# Controller.net
KiCad netlist of a schematic drawn in EAGLE
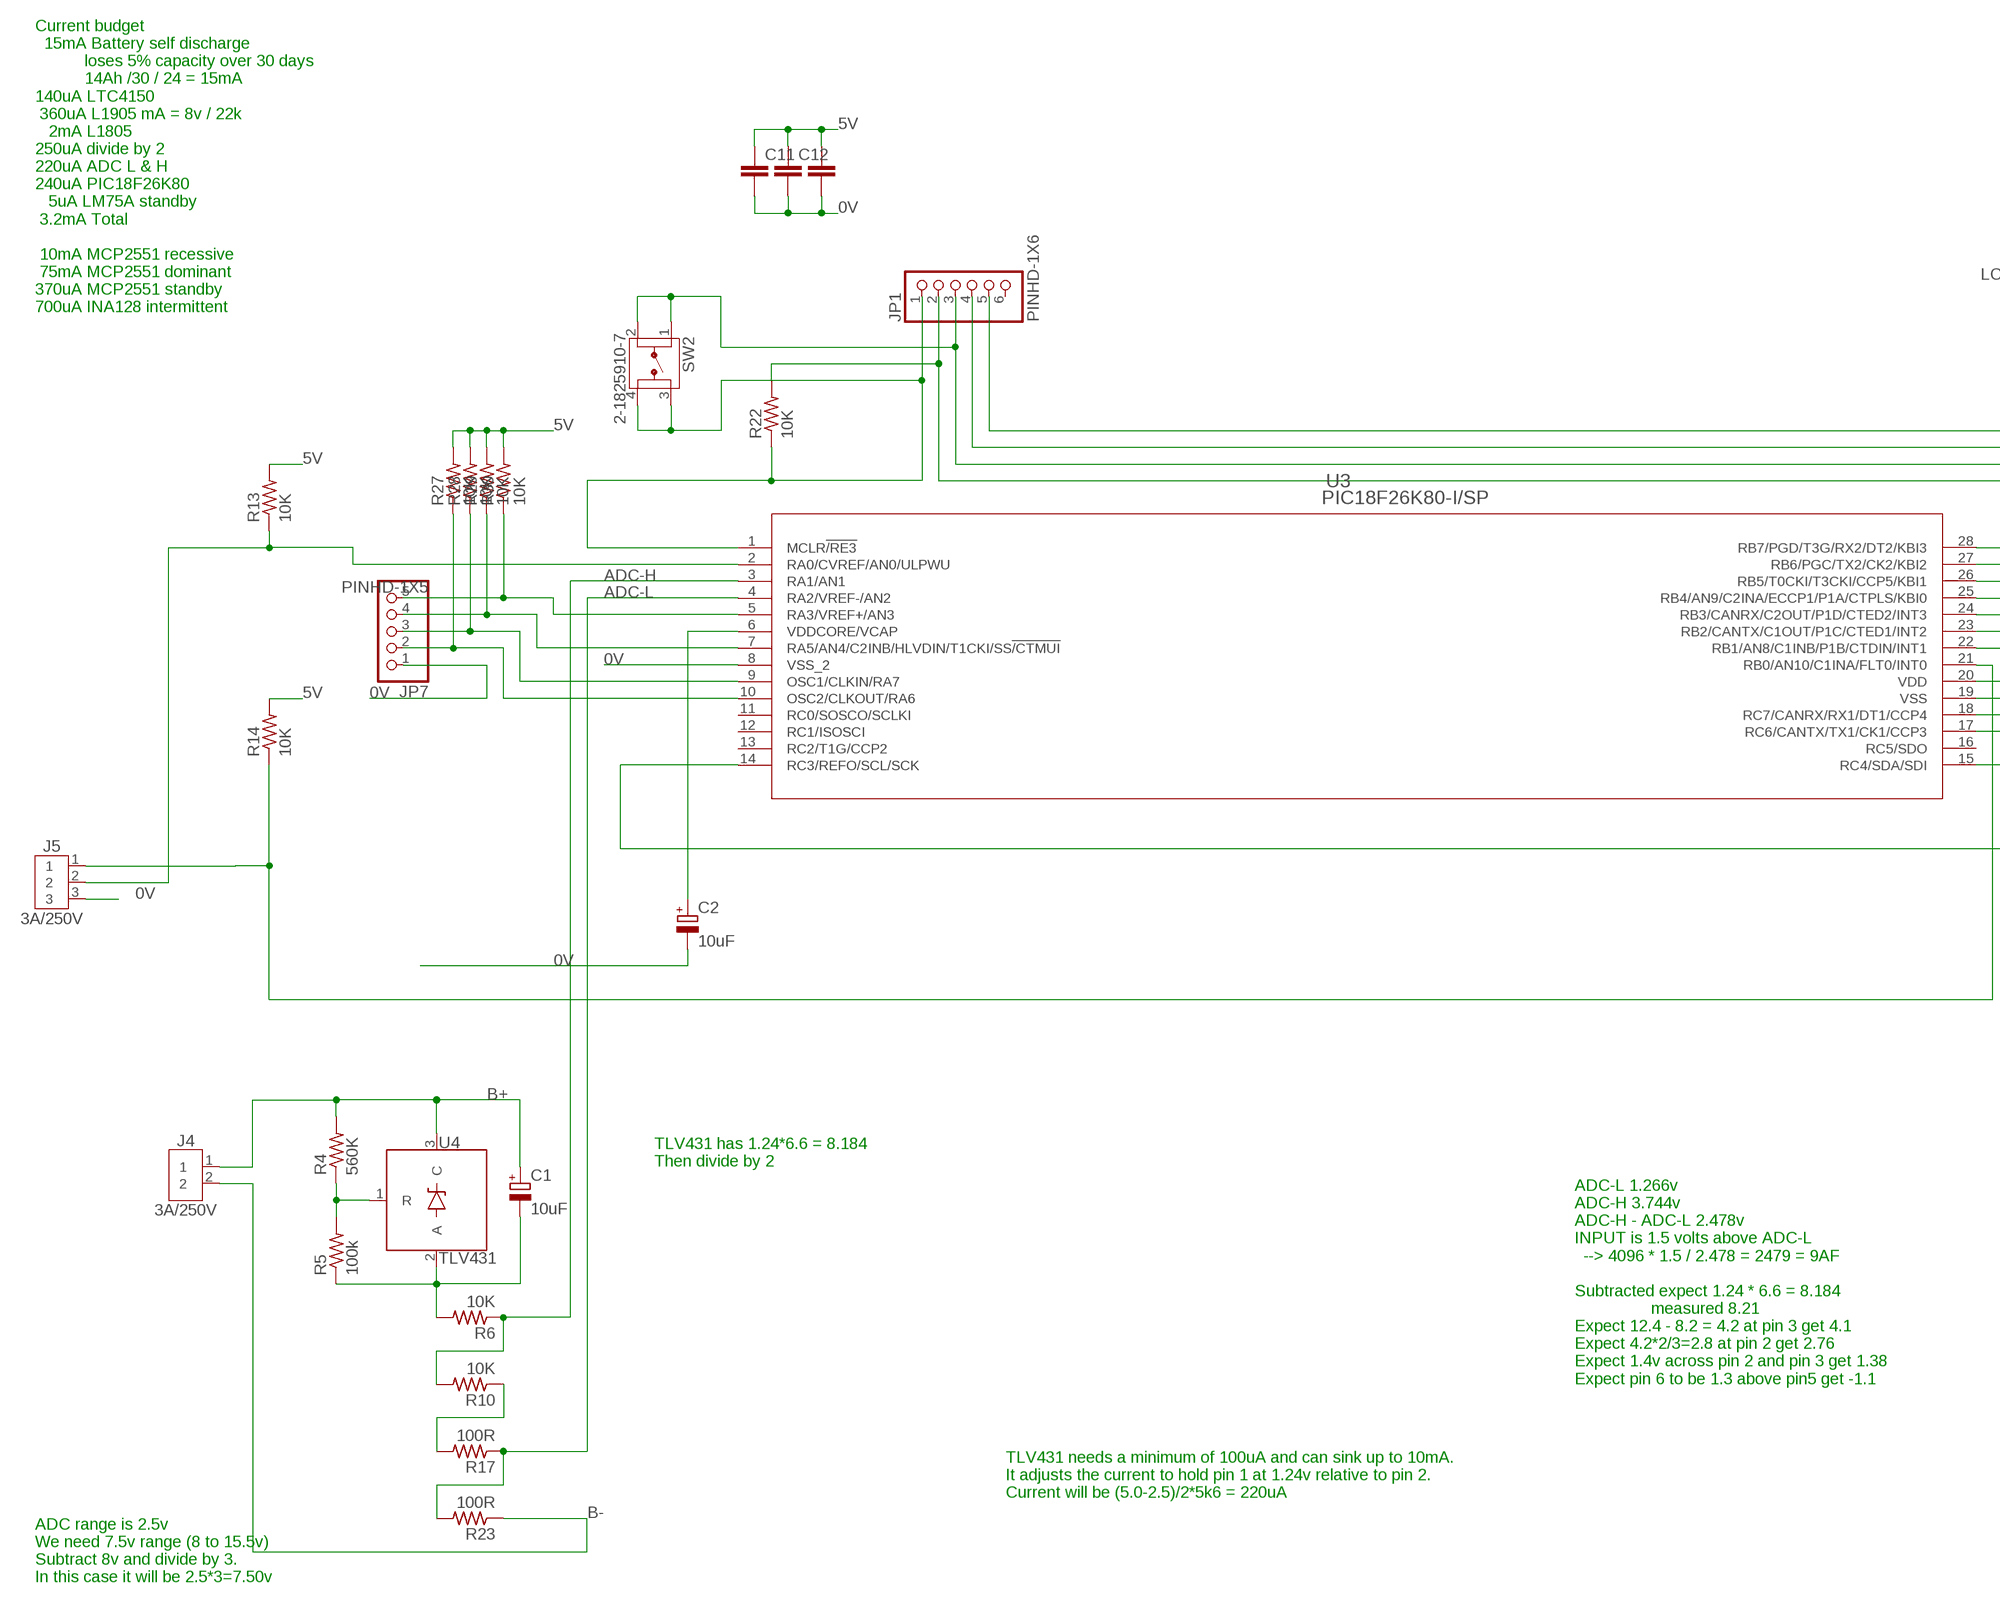
[diagram p0: schematic, sheet 1, part 1 of 2]
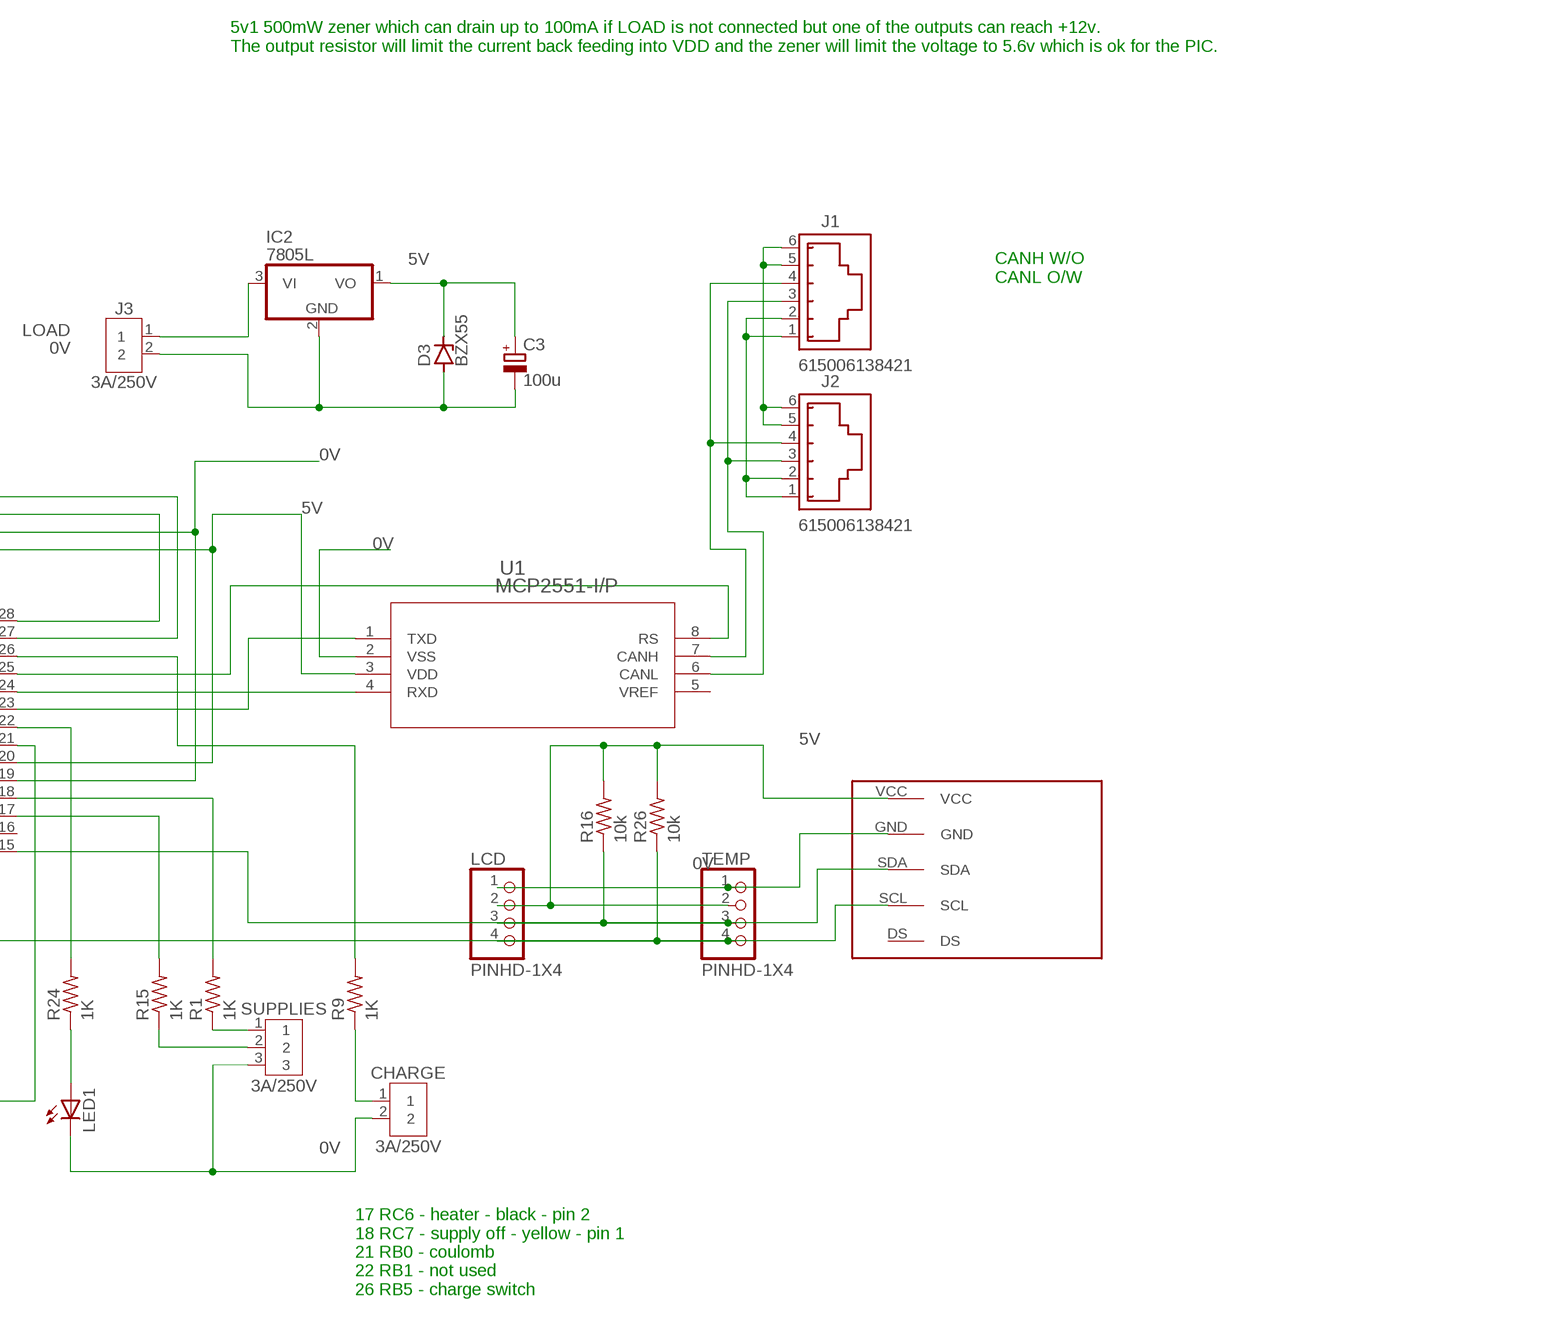
[diagram p1: schematic, sheet 1, part 2 of 2]

(export (version "E")
  (design (tool "Eeschema 10.0.6"))
  (components
    (comp (ref "C1")
      (value "10uF")
      (footprint "eagle-import:E3,5-8")
      (libsource (lib "eagle-import") (part "CPOL-EUE3.5-8"))
    )
    (comp (ref "C2")
      (value "10uF")
      (footprint "eagle-import:E3,5-8")
      (libsource (lib "eagle-import") (part "CPOL-EUE3.5-8"))
    )
    (comp (ref "C3")
      (value "100u")
      (footprint "eagle-import:E3,5-8")
      (libsource (lib "eagle-import") (part "CPOL-EUE3.5-8"))
    )
    (comp (ref "C7")
      (value "C2,5-3")
      (footprint "eagle-import:C2.5-3")
      (libsource (lib "eagle-import") (part "C2,5-3"))
    )
    (comp (ref "C11")
      (value "C2,5-3")
      (footprint "eagle-import:C2.5-3")
      (libsource (lib "eagle-import") (part "C2,5-3"))
    )
    (comp (ref "C12")
      (value "C2,5-3")
      (footprint "eagle-import:C2.5-3")
      (libsource (lib "eagle-import") (part "C2,5-3"))
    )
    (comp (ref "CHARGE")
      (value "3A/250V")
      (footprint "eagle-import:B2B-XH-A")
      (fields (field (name "MANUFACTURER") "JST (XH CONNECTOR)") (field (name "MPN") "B2B-XH-A"))
      (libsource (lib "eagle-import") (part "B2B-XH-A"))
    )
    (comp (ref "D3")
      (value "BZX55")
      (footprint "eagle-import:DO35Z10")
      (libsource (lib "eagle-import") (part "BZX55"))
    )
    (comp (ref "IC2")
      (value "7805L")
      (footprint "eagle-import:TO92")
      (libsource (lib "eagle-import") (part "78L05"))
    )
    (comp (ref "J1")
      (value "615006138421")
      (footprint "eagle-import:615006138421")
      (libsource (lib "eagle-import") (part "615006138421"))
    )
    (comp (ref "J2")
      (value "615006138421")
      (footprint "eagle-import:615006138421")
      (libsource (lib "eagle-import") (part "615006138421"))
    )
    (comp (ref "J3")
      (value "3A/250V")
      (footprint "eagle-import:B2B-XH-A")
      (fields (field (name "MANUFACTURER") "JST (XH CONNECTOR)") (field (name "MPN") "B2B-XH-A"))
      (libsource (lib "eagle-import") (part "B2B-XH-A"))
    )
    (comp (ref "J4")
      (value "3A/250V")
      (footprint "eagle-import:B2B-XH-A")
      (fields (field (name "MANUFACTURER") "JST (XH CONNECTOR)") (field (name "MPN") "B2B-XH-A"))
      (libsource (lib "eagle-import") (part "B2B-XH-A"))
    )
    (comp (ref "J5")
      (value "3A/250V")
      (footprint "eagle-import:B3B-XH-A")
      (fields (field (name "MANUFACTURER") "JST (XH connector)") (field (name "MPN") "B3B-XH-A"))
      (libsource (lib "eagle-import") (part "B3B-XH-A"))
    )
    (comp (ref "JP1")
      (value "PINHD-1X6")
      (footprint "eagle-import:1X06")
      (libsource (lib "eagle-import") (part "PINHD-1X6"))
    )
    (comp (ref "JP7")
      (value "PINHD-1X5")
      (footprint "eagle-import:1X05")
      (libsource (lib "eagle-import") (part "PINHD-1X5"))
    )
    (comp (ref "LCD")
      (value "PINHD-1X4")
      (footprint "eagle-import:1X04")
      (libsource (lib "eagle-import") (part "PINHD-1X4"))
    )
    (comp (ref "LED1")
      (value "LED3MM")
      (footprint "eagle-import:LED3MM")
      (libsource (lib "eagle-import") (part "LED3MM"))
    )
    (comp (ref "R1")
      (value "1K")
      (footprint "eagle-import:0204_7")
      (libsource (lib "eagle-import") (part "RES_7"))
    )
    (comp (ref "R4")
      (value "560K")
      (footprint "eagle-import:0204_7")
      (libsource (lib "eagle-import") (part "RES_7"))
    )
    (comp (ref "R5")
      (value "100k")
      (footprint "eagle-import:0204_7")
      (libsource (lib "eagle-import") (part "RES_7"))
    )
    (comp (ref "R6")
      (value "10K")
      (footprint "eagle-import:0204_7")
      (libsource (lib "eagle-import") (part "RES_7"))
    )
    (comp (ref "R9")
      (value "1K")
      (footprint "eagle-import:0204_7")
      (libsource (lib "eagle-import") (part "RES_7"))
    )
    (comp (ref "R10")
      (value "10K")
      (footprint "eagle-import:0204_7")
      (libsource (lib "eagle-import") (part "RES_7"))
    )
    (comp (ref "R13")
      (value "10K")
      (footprint "eagle-import:0204_7")
      (libsource (lib "eagle-import") (part "RES_7"))
    )
    (comp (ref "R14")
      (value "10K")
      (footprint "eagle-import:0204_7")
      (libsource (lib "eagle-import") (part "RES_7"))
    )
    (comp (ref "R15")
      (value "1K")
      (footprint "eagle-import:0204_7")
      (libsource (lib "eagle-import") (part "RES_7"))
    )
    (comp (ref "R16")
      (value "10k")
      (footprint "eagle-import:0204_7")
      (libsource (lib "eagle-import") (part "RES_7"))
    )
    (comp (ref "R17")
      (value "100R")
      (footprint "eagle-import:0204_7")
      (libsource (lib "eagle-import") (part "RES_7"))
    )
    (comp (ref "R22")
      (value "10K")
      (footprint "eagle-import:0204_7")
      (libsource (lib "eagle-import") (part "RES_7"))
    )
    (comp (ref "R23")
      (value "100R")
      (footprint "eagle-import:0204_7")
      (libsource (lib "eagle-import") (part "RES_7"))
    )
    (comp (ref "R24")
      (value "1K")
      (footprint "eagle-import:0204_7")
      (libsource (lib "eagle-import") (part "RES_7"))
    )
    (comp (ref "R26")
      (value "10k")
      (footprint "eagle-import:0204_7")
      (libsource (lib "eagle-import") (part "RES_7"))
    )
    (comp (ref "R27")
      (value "10K")
      (footprint "eagle-import:0204_7-90")
      (libsource (lib "eagle-import") (part "RES_70204/7-90"))
    )
    (comp (ref "R28")
      (value "10K")
      (footprint "eagle-import:0204_7-90")
      (libsource (lib "eagle-import") (part "RES_70204/7-90"))
    )
    (comp (ref "R29")
      (value "10K")
      (footprint "eagle-import:0204_7-90")
      (libsource (lib "eagle-import") (part "RES_70204/7-90"))
    )
    (comp (ref "R30")
      (value "10K")
      (footprint "eagle-import:0204_7-90")
      (libsource (lib "eagle-import") (part "RES_70204/7-90"))
    )
    (comp (ref "SUPPLIES")
      (value "3A/250V")
      (footprint "eagle-import:B3B-XH-A")
      (fields (field (name "MANUFACTURER") "JST (XH connector)") (field (name "MPN") "B3B-XH-A"))
      (libsource (lib "eagle-import") (part "B3B-XH-A"))
    )
    (comp (ref "SW2")
      (value "2-1825910-7")
      (footprint "eagle-import:2-1825910-7")
      (fields
        (field (name "DIGIKEY_PARTNO") "450-1642-ND")
        (field (name "MANUFACTURER") "TE Connectivity ALCOSWITCH Switches")
        (field (name "CREATED_BY") "PCBLayout.com")
      )
      (libsource (lib "eagle-import") (part "2-1825910-7"))
    )
    (comp (ref "TEMP")
      (value "PINHD-1X4")
      (footprint "eagle-import:1X04")
      (libsource (lib "eagle-import") (part "PINHD-1X4"))
    )
    (comp (ref "U$1")
      (value "LM75")
      (footprint "eagle-import:LM75")
      (libsource (lib "eagle-import") (part "LM75"))
    )
    (comp (ref "U1")
      (value "MCP2551-I/P")
      (footprint "eagle-import:PDIP8_300MC_MCH")
      (fields (field (name "COPYRIGHT") "Copyright (C) 2021 Ultra Librarian. All rights reserved."))
      (libsource (lib "eagle-import") (part "MCP2551-I/P"))
    )
    (comp (ref "U3")
      (value "PIC18F26K80-I/SP")
      (footprint "eagle-import:SPDIP28_300MC_MCH")
      (fields
        (field (name "MANUFACTURER_PART_NUMBER") "pic18f26k80-i/sp")
        (field (name "COPYRIGHT") "Copyright (C) 2021 Ultra Librarian. All rights reserved.")
      )
      (libsource (lib "eagle-import") (part "PIC18F26K80-I/SP"))
    )
    (comp (ref "U4")
      (value "TLV431")
      (footprint "eagle-import:TO92")
      (libsource (lib "eagle-import") (part "TLV431"))
    )
  )
  (nets
    (net (code "1") (name "/0V") (class "Default")
      (node (ref "C11") (pin "2") (pinfunction "2_2") (pintype "passive"))
      (node (ref "C12") (pin "2") (pinfunction "2_2") (pintype "passive"))
      (node (ref "C2") (pin "-") (pinfunction "-_-") (pintype "passive"))
      (node (ref "C3") (pin "-") (pinfunction "-_-") (pintype "passive"))
      (node (ref "C7") (pin "2") (pinfunction "2_2") (pintype "passive"))
      (node (ref "CHARGE") (pin "2") (pinfunction "2_2") (pintype "bidirectional"))
      (node (ref "D3") (pin "A") (pinfunction "A_A") (pintype "passive"))
      (node (ref "IC2") (pin "2") (pinfunction "GND_2") (pintype "passive"))
      (node (ref "J3") (pin "2") (pinfunction "2_2") (pintype "bidirectional"))
      (node (ref "J5") (pin "3") (pinfunction "3_3") (pintype "bidirectional"))
      (node (ref "JP1") (pin "3") (pinfunction "3_3") (pintype "passive"))
      (node (ref "JP7") (pin "1") (pinfunction "1_1") (pintype "passive"))
      (node (ref "LCD") (pin "1") (pinfunction "1_1") (pintype "passive"))
      (node (ref "LED1") (pin "K") (pinfunction "C_K") (pintype "passive"))
      (node (ref "SUPPLIES") (pin "3") (pinfunction "3_3") (pintype "bidirectional"))
      (node (ref "SW2") (pin "1") (pinfunction "1_1") (pintype "passive"))
      (node (ref "SW2") (pin "2") (pinfunction "2_2") (pintype "passive"))
      (node (ref "TEMP") (pin "1") (pinfunction "1_1") (pintype "passive"))
      (node (ref "U$1") (pin "GND") (pinfunction "GND_GND") (pintype "power_in"))
      (node (ref "U1") (pin "2") (pinfunction "VSS_2") (pintype "passive"))
      (node (ref "U3") (pin "19") (pinfunction "VSS_19") (pintype "power_in"))
      (node (ref "U3") (pin "8") (pinfunction "VSS_2_8") (pintype "power_in"))
    )
    (net (code "2") (name "/5V") (class "Default")
      (node (ref "C11") (pin "1") (pinfunction "1_1") (pintype "passive"))
      (node (ref "C12") (pin "1") (pinfunction "1_1") (pintype "passive"))
      (node (ref "C3") (pin "+") (pinfunction "+_+") (pintype "passive"))
      (node (ref "C7") (pin "1") (pinfunction "1_1") (pintype "passive"))
      (node (ref "D3") (pin "C") (pinfunction "C_C") (pintype "passive"))
      (node (ref "IC2") (pin "1") (pinfunction "VO_1") (pintype "passive"))
      (node (ref "JP1") (pin "2") (pinfunction "2_2") (pintype "passive"))
      (node (ref "LCD") (pin "2") (pinfunction "2_2") (pintype "passive"))
      (node (ref "R13") (pin "2") (pinfunction "2_2") (pintype "passive"))
      (node (ref "R14") (pin "2") (pinfunction "2_2") (pintype "passive"))
      (node (ref "R16") (pin "2") (pinfunction "2_2") (pintype "passive"))
      (node (ref "R22") (pin "2") (pinfunction "2_2") (pintype "passive"))
      (node (ref "R26") (pin "2") (pinfunction "2_2") (pintype "passive"))
      (node (ref "R27") (pin "2") (pinfunction "2_2") (pintype "passive"))
      (node (ref "R28") (pin "2") (pinfunction "2_2") (pintype "passive"))
      (node (ref "R29") (pin "2") (pinfunction "2_2") (pintype "passive"))
      (node (ref "R30") (pin "2") (pinfunction "2_2") (pintype "passive"))
      (node (ref "TEMP") (pin "2") (pinfunction "2_2") (pintype "passive"))
      (node (ref "U$1") (pin "VCC") (pinfunction "VCC_VCC") (pintype "power_in"))
      (node (ref "U1") (pin "3") (pinfunction "VDD_3") (pintype "passive"))
      (node (ref "U3") (pin "20") (pinfunction "VDD_20") (pintype "power_in"))
    )
    (net (code "3") (name "/ADC-H") (class "Default")
      (node (ref "R10") (pin "2") (pinfunction "2_2") (pintype "passive"))
      (node (ref "R6") (pin "1") (pinfunction "1_1") (pintype "passive"))
      (node (ref "U3") (pin "3") (pinfunction "RA1/AN1_3") (pintype "bidirectional"))
    )
    (net (code "4") (name "/ADC-L") (class "Default")
      (node (ref "R17") (pin "1") (pinfunction "1_1") (pintype "passive"))
      (node (ref "R23") (pin "2") (pinfunction "2_2") (pintype "passive"))
      (node (ref "U3") (pin "4") (pinfunction "RA2/VREF-/AN2_4") (pintype "bidirectional"))
    )
    (net (code "5") (name "/B+") (class "Default")
      (node (ref "C1") (pin "+") (pinfunction "+_+") (pintype "passive"))
      (node (ref "J4") (pin "1") (pinfunction "1_1") (pintype "bidirectional"))
      (node (ref "R4") (pin "2") (pinfunction "2_2") (pintype "passive"))
      (node (ref "U4") (pin "3") (pinfunction "C_3") (pintype "bidirectional"))
    )
    (net (code "6") (name "/B-") (class "Default")
      (node (ref "J4") (pin "2") (pinfunction "2_2") (pintype "bidirectional"))
      (node (ref "R23") (pin "1") (pinfunction "1_1") (pintype "passive"))
    )
    (net (code "7") (name "/LOAD") (class "Default")
      (node (ref "IC2") (pin "3") (pinfunction "VI_3") (pintype "input"))
      (node (ref "J3") (pin "1") (pinfunction "1_1") (pintype "bidirectional"))
    )
    (net (code "8") (name "Net-(CHARGE-Pad1)") (class "Default")
      (node (ref "CHARGE") (pin "1") (pinfunction "1_1") (pintype "bidirectional"))
      (node (ref "R9") (pin "1") (pinfunction "1_1") (pintype "passive"))
    )
    (net (code "9") (name "Net-(J1-Pad1)") (class "Default")
      (node (ref "J1") (pin "1") (pinfunction "1_1") (pintype "passive"))
      (node (ref "J1") (pin "2") (pinfunction "2_2") (pintype "passive"))
      (node (ref "J2") (pin "1") (pinfunction "1_1") (pintype "passive"))
      (node (ref "J2") (pin "2") (pinfunction "2_2") (pintype "passive"))
    )
    (net (code "10") (name "Net-(J1-Pad5)") (class "Default")
      (node (ref "J1") (pin "5") (pinfunction "5_5") (pintype "passive"))
      (node (ref "J1") (pin "6") (pinfunction "6_6") (pintype "passive"))
      (node (ref "J2") (pin "5") (pinfunction "5_5") (pintype "passive"))
      (node (ref "J2") (pin "6") (pinfunction "6_6") (pintype "passive"))
    )
    (net (code "11") (name "Net-(LED1-PadA)") (class "Default")
      (node (ref "LED1") (pin "A") (pinfunction "A_A") (pintype "passive"))
      (node (ref "R24") (pin "1") (pinfunction "1_1") (pintype "passive"))
    )
    (net (code "12") (name "Net-(R1-Pad1)") (class "Default")
      (node (ref "R1") (pin "1") (pinfunction "1_1") (pintype "passive"))
      (node (ref "SUPPLIES") (pin "1") (pinfunction "1_1") (pintype "bidirectional"))
    )
    (net (code "13") (name "Net-(R10-Pad1)") (class "Default")
      (node (ref "R10") (pin "1") (pinfunction "1_1") (pintype "passive"))
      (node (ref "R17") (pin "2") (pinfunction "2_2") (pintype "passive"))
    )
    (net (code "14") (name "Net-(R15-Pad1)") (class "Default")
      (node (ref "R15") (pin "1") (pinfunction "1_1") (pintype "passive"))
      (node (ref "SUPPLIES") (pin "2") (pinfunction "2_2") (pintype "bidirectional"))
    )
    (net (code "15") (name "Net-(U1-CANH)") (class "Default")
      (node (ref "J1") (pin "4") (pinfunction "4_4") (pintype "passive"))
      (node (ref "J2") (pin "4") (pinfunction "4_4") (pintype "passive"))
      (node (ref "U1") (pin "7") (pinfunction "CANH_7") (pintype "passive"))
    )
    (net (code "16") (name "Net-(U1-CANL)") (class "Default")
      (node (ref "J1") (pin "3") (pinfunction "3_3") (pintype "passive"))
      (node (ref "J2") (pin "3") (pinfunction "3_3") (pintype "passive"))
      (node (ref "U1") (pin "6") (pinfunction "CANL_6") (pintype "passive"))
    )
    (net (code "17") (name "Net-(U1-RS)") (class "Default")
      (node (ref "U1") (pin "8") (pinfunction "RS_8") (pintype "passive"))
      (node (ref "U3") (pin "25") (pinfunction "RB4/AN9/C2INA/ECCP1/P1A/CTPLS/KBI0_25") (pintype "bidirectional"))
    )
    (net (code "18") (name "Net-(U1-RXD)") (class "Default")
      (node (ref "U1") (pin "4") (pinfunction "RXD_4") (pintype "passive"))
      (node (ref "U3") (pin "24") (pinfunction "RB3/CANRX/C2OUT/P1D/CTED2/INT3_24") (pintype "bidirectional"))
    )
    (net (code "19") (name "Net-(U1-TXD)") (class "Default")
      (node (ref "U1") (pin "1") (pinfunction "TXD_1") (pintype "passive"))
      (node (ref "U3") (pin "23") (pinfunction "RB2/CANTX/C1OUT/P1C/CTED1/INT2_23") (pintype "bidirectional"))
    )
    (net (code "20") (name "Net-(U3-MCLR~{{slash}RE3})") (class "Default")
      (node (ref "JP1") (pin "1") (pinfunction "1_1") (pintype "passive"))
      (node (ref "R22") (pin "1") (pinfunction "1_1") (pintype "passive"))
      (node (ref "SW2") (pin "3") (pinfunction "3_3") (pintype "passive"))
      (node (ref "SW2") (pin "4") (pinfunction "4_4") (pintype "passive"))
      (node (ref "U3") (pin "1") (pinfunction "MCLR~{/RE3}_1") (pintype "bidirectional"))
    )
    (net (code "21") (name "Net-(U3-OSC1{slash}CLKIN{slash}RA7)") (class "Default")
      (node (ref "JP7") (pin "3") (pinfunction "3_3") (pintype "passive"))
      (node (ref "R28") (pin "1") (pinfunction "1_1") (pintype "passive"))
      (node (ref "U3") (pin "9") (pinfunction "OSC1/CLKIN/RA7_9") (pintype "bidirectional"))
    )
    (net (code "22") (name "Net-(U3-OSC2{slash}CLKOUT{slash}RA6)") (class "Default")
      (node (ref "JP7") (pin "2") (pinfunction "2_2") (pintype "passive"))
      (node (ref "R27") (pin "1") (pinfunction "1_1") (pintype "passive"))
      (node (ref "U3") (pin "10") (pinfunction "OSC2/CLKOUT/RA6_10") (pintype "bidirectional"))
    )
    (net (code "23") (name "Net-(U3-RA0{slash}CVREF{slash}AN0{slash}ULPWU)") (class "Default")
      (node (ref "J5") (pin "2") (pinfunction "2_2") (pintype "bidirectional"))
      (node (ref "R13") (pin "1") (pinfunction "1_1") (pintype "passive"))
      (node (ref "U3") (pin "2") (pinfunction "RA0/CVREF/AN0/ULPWU_2") (pintype "bidirectional"))
    )
    (net (code "24") (name "Net-(U3-RA3{slash}VREF+{slash}AN3)") (class "Default")
      (node (ref "JP7") (pin "5") (pinfunction "5_5") (pintype "passive"))
      (node (ref "R30") (pin "1") (pinfunction "1_1") (pintype "passive"))
      (node (ref "U3") (pin "5") (pinfunction "RA3/VREF+/AN3_5") (pintype "bidirectional"))
    )
    (net (code "25") (name "Net-(U3-RA5{slash}AN4{slash}C2INB{slash}HLVDIN{slash}T1CKI{slash}SS~{{slash}CTMUI})") (class "Default")
      (node (ref "JP7") (pin "4") (pinfunction "4_4") (pintype "passive"))
      (node (ref "R29") (pin "1") (pinfunction "1_1") (pintype "passive"))
      (node (ref "U3") (pin "7") (pinfunction "RA5/AN4/C2INB/HLVDIN/T1CKI/SS~{/CTMUI}_7") (pintype "bidirectional"))
    )
    (net (code "26") (name "Net-(U3-RB0{slash}AN10{slash}C1INA{slash}FLT0{slash}INT0)") (class "Default")
      (node (ref "J5") (pin "1") (pinfunction "1_1") (pintype "bidirectional"))
      (node (ref "R14") (pin "1") (pinfunction "1_1") (pintype "passive"))
      (node (ref "U3") (pin "21") (pinfunction "RB0/AN10/C1INA/FLT0/INT0_21") (pintype "bidirectional"))
    )
    (net (code "27") (name "Net-(U3-RB1{slash}AN8{slash}C1INB{slash}P1B{slash}CTDIN{slash}INT1)") (class "Default")
      (node (ref "R24") (pin "2") (pinfunction "2_2") (pintype "passive"))
      (node (ref "U3") (pin "22") (pinfunction "RB1/AN8/C1INB/P1B/CTDIN/INT1_22") (pintype "bidirectional"))
    )
    (net (code "28") (name "Net-(U3-RB5{slash}T0CKI{slash}T3CKI{slash}CCP5{slash}KBI1)") (class "Default")
      (node (ref "R9") (pin "2") (pinfunction "2_2") (pintype "passive"))
      (node (ref "U3") (pin "26") (pinfunction "RB5/T0CKI/T3CKI/CCP5/KBI1_26") (pintype "bidirectional"))
    )
    (net (code "29") (name "Net-(U3-RB6{slash}PGC{slash}TX2{slash}CK2{slash}KBI2)") (class "Default")
      (node (ref "JP1") (pin "5") (pinfunction "5_5") (pintype "passive"))
      (node (ref "U3") (pin "27") (pinfunction "RB6/PGC/TX2/CK2/KBI2_27") (pintype "bidirectional"))
    )
    (net (code "30") (name "Net-(U3-RB7{slash}PGD{slash}T3G{slash}RX2{slash}DT2{slash}KBI3)") (class "Default")
      (node (ref "JP1") (pin "4") (pinfunction "4_4") (pintype "passive"))
      (node (ref "U3") (pin "28") (pinfunction "RB7/PGD/T3G/RX2/DT2/KBI3_28") (pintype "bidirectional"))
    )
    (net (code "31") (name "Net-(U3-RC3{slash}REFO{slash}SCL{slash}SCK)") (class "Default")
      (node (ref "LCD") (pin "4") (pinfunction "4_4") (pintype "passive"))
      (node (ref "R26") (pin "1") (pinfunction "1_1") (pintype "passive"))
      (node (ref "TEMP") (pin "4") (pinfunction "4_4") (pintype "passive"))
      (node (ref "U$1") (pin "SCL") (pinfunction "SCL_SCL") (pintype "input"))
      (node (ref "U3") (pin "14") (pinfunction "RC3/REFO/SCL/SCK_14") (pintype "bidirectional"))
    )
    (net (code "32") (name "Net-(U3-RC4{slash}SDA{slash}SDI)") (class "Default")
      (node (ref "LCD") (pin "3") (pinfunction "3_3") (pintype "passive"))
      (node (ref "R16") (pin "1") (pinfunction "1_1") (pintype "passive"))
      (node (ref "TEMP") (pin "3") (pinfunction "3_3") (pintype "passive"))
      (node (ref "U$1") (pin "SDA") (pinfunction "SDA_SDA") (pintype "bidirectional"))
      (node (ref "U3") (pin "15") (pinfunction "RC4/SDA/SDI_15") (pintype "bidirectional"))
    )
    (net (code "33") (name "Net-(U3-RC6{slash}CANTX{slash}TX1{slash}CK1{slash}CCP3)") (class "Default")
      (node (ref "R15") (pin "2") (pinfunction "2_2") (pintype "passive"))
      (node (ref "U3") (pin "17") (pinfunction "RC6/CANTX/TX1/CK1/CCP3_17") (pintype "bidirectional"))
    )
    (net (code "34") (name "Net-(U3-RC7{slash}CANRX{slash}RX1{slash}DT1{slash}CCP4)") (class "Default")
      (node (ref "R1") (pin "2") (pinfunction "2_2") (pintype "passive"))
      (node (ref "U3") (pin "18") (pinfunction "RC7/CANRX/RX1/DT1/CCP4_18") (pintype "bidirectional"))
    )
    (net (code "35") (name "Net-(U3-VDDCORE{slash}VCAP)") (class "Default")
      (node (ref "C2") (pin "+") (pinfunction "+_+") (pintype "passive"))
      (node (ref "U3") (pin "6") (pinfunction "VDDCORE/VCAP_6") (pintype "power_in"))
    )
    (net (code "36") (name "Net-(U4-A)") (class "Default")
      (node (ref "C1") (pin "-") (pinfunction "-_-") (pintype "passive"))
      (node (ref "R5") (pin "1") (pinfunction "1_1") (pintype "passive"))
      (node (ref "R6") (pin "2") (pinfunction "2_2") (pintype "passive"))
      (node (ref "U4") (pin "2") (pinfunction "A_2") (pintype "bidirectional"))
    )
    (net (code "37") (name "Net-(U4-R)") (class "Default")
      (node (ref "R4") (pin "1") (pinfunction "1_1") (pintype "passive"))
      (node (ref "R5") (pin "2") (pinfunction "2_2") (pintype "passive"))
      (node (ref "U4") (pin "1") (pinfunction "R_1") (pintype "bidirectional"))
    )
    (net (code "38") (name "unconnected-(JP1-Pad6)") (class "Default")
      (node (ref "JP1") (pin "6") (pinfunction "6_6") (pintype "passive"))
    )
    (net (code "39") (name "unconnected-(U$1-PadDS)") (class "Default")
      (node (ref "U$1") (pin "DS") (pinfunction "DS_DS") (pintype "bidirectional"))
    )
    (net (code "40") (name "unconnected-(U1-VREF-Pad5)") (class "Default")
      (node (ref "U1") (pin "5") (pinfunction "VREF_5") (pintype "passive"))
    )
    (net (code "41") (name "unconnected-(U3-RC0{slash}SOSCO{slash}SCLKI-Pad11)") (class "Default")
      (node (ref "U3") (pin "11") (pinfunction "RC0/SOSCO/SCLKI_11") (pintype "bidirectional"))
    )
    (net (code "42") (name "unconnected-(U3-RC1{slash}ISOSCI-Pad12)") (class "Default")
      (node (ref "U3") (pin "12") (pinfunction "RC1/ISOSCI_12") (pintype "bidirectional"))
    )
    (net (code "43") (name "unconnected-(U3-RC2{slash}T1G{slash}CCP2-Pad13)") (class "Default")
      (node (ref "U3") (pin "13") (pinfunction "RC2/T1G/CCP2_13") (pintype "bidirectional"))
    )
    (net (code "44") (name "unconnected-(U3-RC5{slash}SDO-Pad16)") (class "Default")
      (node (ref "U3") (pin "16") (pinfunction "RC5/SDO_16") (pintype "bidirectional"))
    )
  )
)
